# Thermistor.net
KiCad netlist of a schematic drawn in Altium Designer
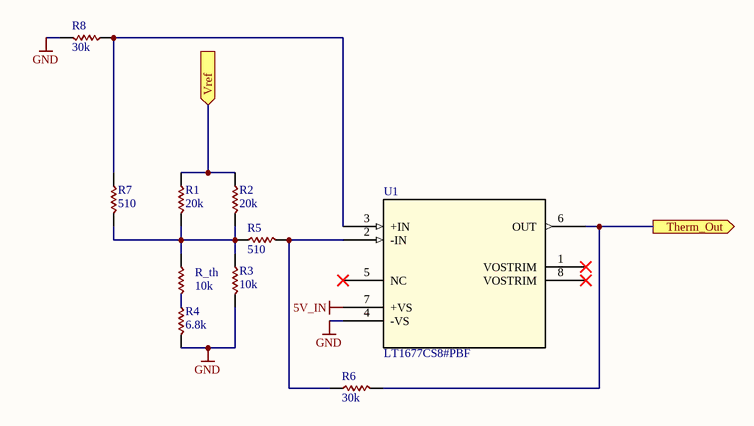
[diagram p0: Thermistor.SchDoc]

(export (version "E")
  (design (tool "Eeschema 10.0.6"))
  (components
    (comp (ref "R1")
      (value "20k")
      (footprint "0603")
      (description "603 Resistor")
      (libsource (lib "PSSL3") (part "RES 0603"))
    )
    (comp (ref "R2")
      (value "20k")
      (footprint "0603")
      (description "603 Resistor")
      (libsource (lib "PSSL3") (part "RES 0603"))
    )
    (comp (ref "R3")
      (value "10k")
      (footprint "0603")
      (description "603 Resistor")
      (libsource (lib "PSSL3") (part "RES 0603"))
    )
    (comp (ref "R4")
      (value "6.8k")
      (footprint "0603")
      (description "603 Resistor")
      (libsource (lib "PSSL3") (part "RES 0603"))
    )
    (comp (ref "R5")
      (value "510")
      (footprint "0603")
      (description "603 Resistor")
      (libsource (lib "PSSL3") (part "RES 0603"))
    )
    (comp (ref "R6")
      (value "30k")
      (footprint "0603")
      (description "603 Resistor")
      (libsource (lib "PSSL3") (part "RES 0603"))
    )
    (comp (ref "R7")
      (value "510")
      (footprint "0603")
      (description "603 Resistor")
      (libsource (lib "PSSL3") (part "RES 0603"))
    )
    (comp (ref "R8")
      (value "30k")
      (footprint "0603")
      (description "603 Resistor")
      (libsource (lib "PSSL3") (part "RES 0603"))
    )
    (comp (ref "R_th")
      (value "10k")
      (footprint "0603")
      (description "603 Resistor")
      (libsource (lib "PSSL3") (part "RES 0603"))
    )
    (comp (ref "U1")
      (value "LT1677CS8#PBF")
      (footprint "SO-8_S_LIT")
      (description "Low Noise, Rail-to-Rail Precision Op Amp")
      (fields (field (name "COPYRIGHT") "Copyright (C) 2018 Accelerated Designs. All rights reserved"))
      (libsource (lib "BeaconBoard") (part "LT1677CS8#PBF"))
    )
  )
  (nets
    (net (code "1") (name "/Therm_Out") (class "Default")
      (node (ref "R6") (pin "1") (pintype "passive"))
      (node (ref "U1") (pin "6") (pinfunction "OUT_6") (pintype "output"))
    )
    (net (code "2") (name "/Vref") (class "Default")
      (node (ref "R1") (pin "2") (pintype "passive"))
      (node (ref "R2") (pin "2") (pintype "passive"))
    )
    (net (code "3") (name "5V_IN") (class "Default")
      (node (ref "U1") (pin "7") (pinfunction "+VS_7") (pintype "power_in"))
    )
    (net (code "4") (name "GND") (class "Default")
      (node (ref "R3") (pin "1") (pintype "passive"))
      (node (ref "R4") (pin "1") (pintype "passive"))
      (node (ref "R8") (pin "1") (pintype "passive"))
      (node (ref "U1") (pin "4") (pinfunction "-VS_4") (pintype "power_in"))
    )
    (net (code "5") (name "Net-(R1-Pad1)") (class "Default")
      (node (ref "R1") (pin "1") (pintype "passive"))
      (node (ref "R2") (pin "1") (pintype "passive"))
      (node (ref "R3") (pin "2") (pintype "passive"))
      (node (ref "R5") (pin "2") (pintype "passive"))
      (node (ref "R7") (pin "1") (pintype "passive"))
      (node (ref "R_th") (pin "2") (pintype "passive"))
    )
    (net (code "6") (name "Net-(R4-Pad2)") (class "Default")
      (node (ref "R4") (pin "2") (pintype "passive"))
      (node (ref "R_th") (pin "1") (pintype "passive"))
    )
    (net (code "7") (name "Net-(U1-+IN)") (class "Default")
      (node (ref "R7") (pin "2") (pintype "passive"))
      (node (ref "R8") (pin "2") (pintype "passive"))
      (node (ref "U1") (pin "3") (pinfunction "+IN_3") (pintype "input"))
    )
    (net (code "8") (name "Net-(U1--IN)") (class "Default")
      (node (ref "R5") (pin "1") (pintype "passive"))
      (node (ref "R6") (pin "2") (pintype "passive"))
      (node (ref "U1") (pin "2") (pinfunction "-IN_2") (pintype "input"))
    )
    (net (code "9") (name "unconnected-(U1-NC-Pad5)") (class "Default")
      (node (ref "U1") (pin "5") (pinfunction "NC_5") (pintype "passive+no_connect"))
    )
    (net (code "10") (name "unconnected-(U1-VOSTRIM-Pad1)") (class "Default")
      (node (ref "U1") (pin "1") (pinfunction "VOSTRIM_1") (pintype "passive+no_connect"))
    )
    (net (code "11") (name "unconnected-(U1-VOSTRIM-Pad8)") (class "Default")
      (node (ref "U1") (pin "8") (pinfunction "VOSTRIM_8") (pintype "passive+no_connect"))
    )
  )
)
